# moodyv1_final_rzl.net
KiCad netlist of a schematic drawn in EAGLE
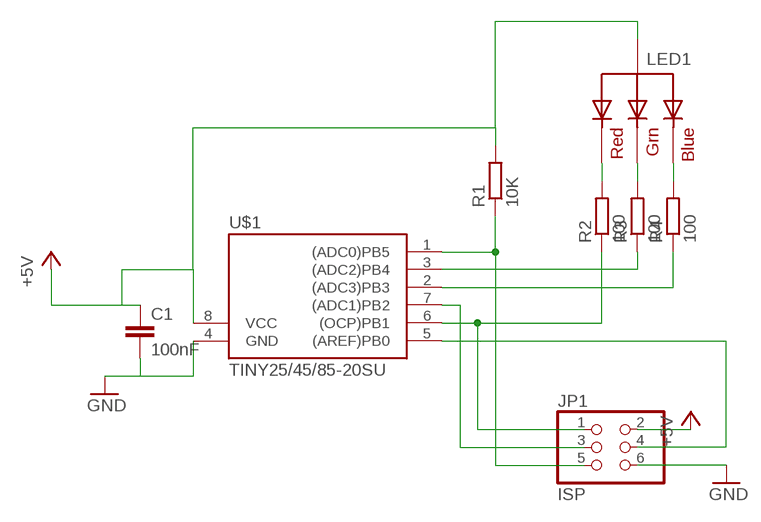
[diagram p0: schematic, sheet 1]

(export (version "E")
  (design (tool "Eeschema 10.0.6"))
  (components
    (comp (ref "C1")
      (value "100nF")
      (footprint "eagle-import:C0805")
      (libsource (lib "eagle-import") (part "C-EUC0805"))
    )
    (comp (ref "JP1")
      (value "ISP")
      (footprint "eagle-import:2X03SMD")
      (libsource (lib "eagle-import") (part "PINHD-2X03_2.54-SMD"))
    )
    (comp (ref "LED1")
      (value "RGBLED_CA-PIRANHA")
      (footprint "eagle-import:PIRANHA5MM")
      (libsource (lib "eagle-import") (part "RGBLED_CA-PIRANHA"))
    )
    (comp (ref "R1")
      (value "10K")
      (footprint "eagle-import:R1206")
      (libsource (lib "eagle-import") (part "R-EU_R1206"))
    )
    (comp (ref "R2")
      (value "100")
      (footprint "eagle-import:R0805")
      (libsource (lib "eagle-import") (part "R-EU_R0805"))
    )
    (comp (ref "R3")
      (value "100")
      (footprint "eagle-import:R0805")
      (libsource (lib "eagle-import") (part "R-EU_R0805"))
    )
    (comp (ref "R4")
      (value "100")
      (footprint "eagle-import:R0805")
      (libsource (lib "eagle-import") (part "R-EU_R0805"))
    )
    (comp (ref "U$1")
      (value "TINY25/45/85-20SU")
      (footprint "eagle-import:SOIC8")
      (libsource (lib "eagle-import") (part "TINY25/45/85-20SU"))
    )
  )
  (nets
    (net (code "1") (name "+5V") (class "Default")
      (node (ref "C1") (pin "1") (pinfunction "1_1") (pintype "passive"))
      (node (ref "JP1") (pin "2") (pinfunction "2_2") (pintype "passive"))
      (node (ref "LED1") (pin "4") (pinfunction "VCC_4") (pintype "bidirectional"))
      (node (ref "R1") (pin "2") (pinfunction "2_2") (pintype "passive"))
      (node (ref "U$1") (pin "8") (pinfunction "VCC_8") (pintype "power_in"))
    )
    (net (code "2") (name "GND") (class "Default")
      (node (ref "C1") (pin "2") (pinfunction "2_2") (pintype "passive"))
      (node (ref "JP1") (pin "6") (pinfunction "6_6") (pintype "passive"))
      (node (ref "U$1") (pin "4") (pinfunction "GND_4") (pintype "power_in"))
    )
    (net (code "3") (name "Net-(LED1-BLUE)") (class "Default")
      (node (ref "LED1") (pin "1") (pinfunction "BLUE_1") (pintype "bidirectional"))
      (node (ref "R4") (pin "2") (pinfunction "2_2") (pintype "passive"))
    )
    (net (code "4") (name "Net-(LED1-GREEN)") (class "Default")
      (node (ref "LED1") (pin "3") (pinfunction "GREEN_3") (pintype "bidirectional"))
      (node (ref "R3") (pin "2") (pinfunction "2_2") (pintype "passive"))
    )
    (net (code "5") (name "Net-(LED1-RED)") (class "Default")
      (node (ref "LED1") (pin "2") (pinfunction "RED_2") (pintype "bidirectional"))
      (node (ref "R2") (pin "2") (pinfunction "2_2") (pintype "passive"))
    )
    (net (code "6") (name "Net-(U$1-(ADC0)PB5)") (class "Default")
      (node (ref "JP1") (pin "5") (pinfunction "5_5") (pintype "passive"))
      (node (ref "R1") (pin "1") (pinfunction "1_1") (pintype "passive"))
      (node (ref "U$1") (pin "1") (pinfunction "(ADC0)PB5_1") (pintype "bidirectional"))
    )
    (net (code "7") (name "Net-(U$1-(ADC1)PB2)") (class "Default")
      (node (ref "JP1") (pin "3") (pinfunction "3_3") (pintype "passive"))
      (node (ref "U$1") (pin "7") (pinfunction "(ADC1)PB2_7") (pintype "bidirectional"))
    )
    (net (code "8") (name "Net-(U$1-(ADC2)PB4)") (class "Default")
      (node (ref "R3") (pin "1") (pinfunction "1_1") (pintype "passive"))
      (node (ref "U$1") (pin "3") (pinfunction "(ADC2)PB4_3") (pintype "bidirectional"))
    )
    (net (code "9") (name "Net-(U$1-(ADC3)PB3)") (class "Default")
      (node (ref "R4") (pin "1") (pinfunction "1_1") (pintype "passive"))
      (node (ref "U$1") (pin "2") (pinfunction "(ADC3)PB3_2") (pintype "bidirectional"))
    )
    (net (code "10") (name "Net-(U$1-(AREF)PB0)") (class "Default")
      (node (ref "JP1") (pin "4") (pinfunction "4_4") (pintype "passive"))
      (node (ref "U$1") (pin "5") (pinfunction "(AREF)PB0_5") (pintype "bidirectional"))
    )
    (net (code "11") (name "Net-(U$1-(OCP)PB1)") (class "Default")
      (node (ref "JP1") (pin "1") (pinfunction "1_1") (pintype "passive"))
      (node (ref "R2") (pin "1") (pinfunction "1_1") (pintype "passive"))
      (node (ref "U$1") (pin "6") (pinfunction "(OCP)PB1_6") (pintype "bidirectional"))
    )
  )
)
